# SLAVE.net
KiCad netlist of a schematic drawn in Altium Designer
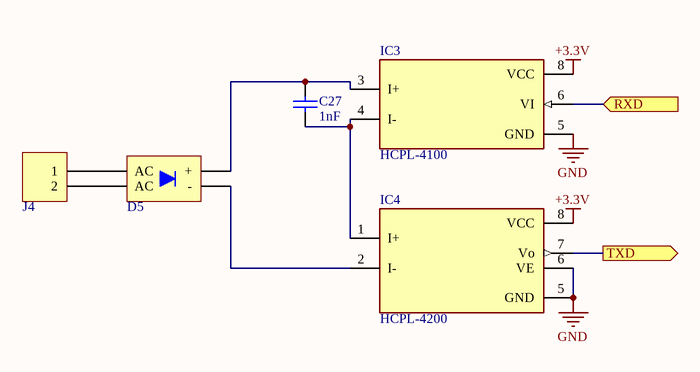
[diagram p0: SLAVE.SchDoc]

(export (version "E")
  (design (tool "Eeschema 10.0.6"))
  (components
    (comp (ref "C27")
      (value "1nF")
      (footprint "PARSALIBRARY:C1206")
      (description "Capacitor")
      (fields (field (name "DESIGNER") "Parsa Malekpour"))
      (libsource (lib "ParsaLibrary") (part "Cap"))
    )
    (comp (ref "D5") (value "HD08") (footprint "MINIDIP") (libsource (lib "ParsaLibrary") (part "HD08")))
    (comp (ref "IC3")
      (value "HCPL-4100")
      (footprint "PARSALIBRARY:DIP-8")
      (description "<b>Isolation Amplifer</b><p> Source: http://www.avagotech.com/docs/AV02-0410EN")
      (fields (field (name "MF") "{'manufacturer': u'Broadcom Limited'}"))
      (libsource (lib "ParsaLibrary") (part "HCPL-4100"))
    )
    (comp (ref "IC4")
      (value "HCPL-4200")
      (footprint "PARSALIBRARY:DIP-8")
      (description "Optically Coupled 20 mA Current Loop Receiver")
      (fields (field (name "MF") "{'manufacturer': u'Broadcom Limited'}") (field (name "MP") "HCPL-4100"))
      (libsource (lib "ParsaLibrary") (part "HCPL-4200"))
    )
    (comp (ref "J4") (value "CONN-2") (footprint "XH-2") (libsource (lib "ParsaLibrary") (part "CONN-2")))
  )
  (nets
    (net (code "1") (name "+3.3V") (class "Default")
      (node (ref "IC3") (pin "8") (pinfunction "VCC_8") (pintype "power_in"))
      (node (ref "IC4") (pin "8") (pinfunction "VCC_8") (pintype "power_in"))
    )
    (net (code "2") (name "/RXD") (class "Default")
      (node (ref "IC3") (pin "6") (pinfunction "VI_6") (pintype "input"))
    )
    (net (code "3") (name "/TXD") (class "Default")
      (node (ref "IC4") (pin "7") (pinfunction "Vo_7") (pintype "output"))
    )
    (net (code "4") (name "GND") (class "Default")
      (node (ref "IC3") (pin "5") (pinfunction "GND_5") (pintype "power_in"))
      (node (ref "IC4") (pin "5") (pinfunction "GND_5") (pintype "power_in"))
      (node (ref "IC4") (pin "6") (pinfunction "VE_6") (pintype "power_in"))
    )
    (net (code "5") (name "Net-(D5-+)") (class "Default")
      (node (ref "C27") (pin "2") (pinfunction "2_2") (pintype "passive"))
      (node (ref "D5") (pin "1") (pinfunction "+_1") (pintype "passive"))
      (node (ref "IC3") (pin "3") (pinfunction "I+_3") (pintype "power_in"))
    )
    (net (code "6") (name "Net-(D5--)") (class "Default")
      (node (ref "D5") (pin "2") (pinfunction "-_2") (pintype "passive"))
      (node (ref "IC4") (pin "2") (pinfunction "I-_2") (pintype "power_in"))
    )
    (net (code "7") (name "Net-(D5-AC-Pad3)") (class "Default")
      (node (ref "D5") (pin "3") (pinfunction "AC_3") (pintype "passive"))
      (node (ref "J4") (pin "2") (pinfunction "2_2") (pintype "passive"))
    )
    (net (code "8") (name "Net-(D5-AC-Pad4)") (class "Default")
      (node (ref "D5") (pin "4") (pinfunction "AC_4") (pintype "passive"))
      (node (ref "J4") (pin "1") (pinfunction "1_1") (pintype "passive"))
    )
    (net (code "9") (name "Net-(IC3-I-)") (class "Default")
      (node (ref "C27") (pin "1") (pinfunction "1_1") (pintype "passive"))
      (node (ref "IC3") (pin "4") (pinfunction "I-_4") (pintype "power_in"))
      (node (ref "IC4") (pin "1") (pinfunction "I+_1") (pintype "power_in"))
    )
  )
)
